# asm.net
KiCad netlist of a schematic drawn in EAGLE
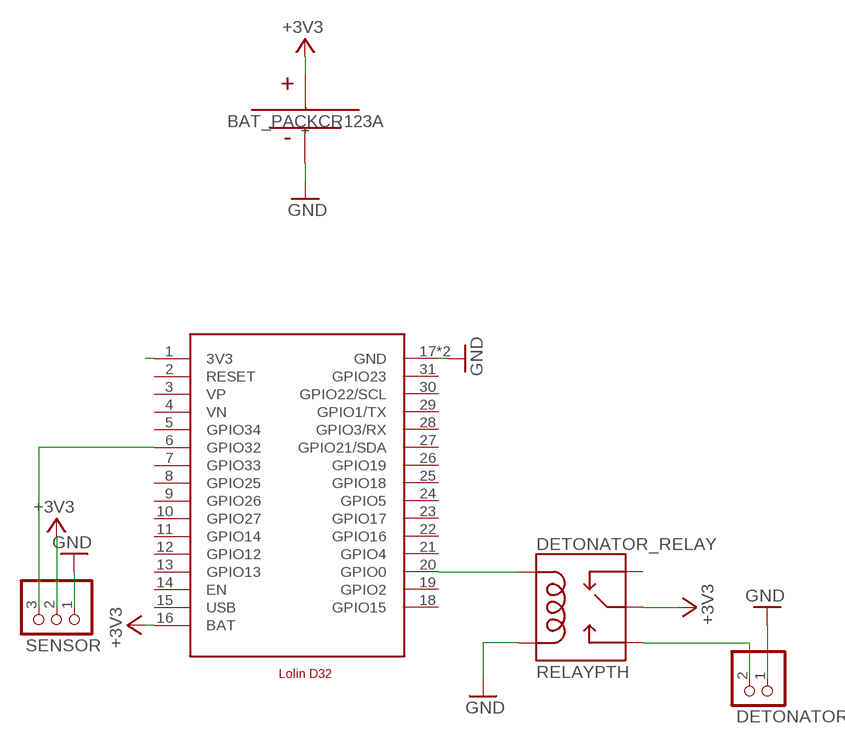
[diagram p0: schematic, sheet 1]

(export (version "E")
  (design (tool "Eeschema 10.0.6"))
  (components
    (comp (ref "CR123A")
      (value "BAT_PACKCR123A")
      (footprint "eagle-import:BH123A")
      (fields (field (name "MANUFACTURER") "MPD") (field (name "MPN") "BH123A"))
      (libsource (lib "eagle-import") (part "BAT_PACKCR123A"))
    )
    (comp (ref "DETONATOR")
      (value "PINHD-1X2")
      (footprint "eagle-import:1X02")
      (libsource (lib "eagle-import") (part "PINHD-1X2"))
    )
    (comp (ref "DETONATOR_RELAY")
      (value "RELAYPTH")
      (footprint "eagle-import:SRD-05VDC-SL-C")
      (libsource (lib "eagle-import") (part "RELAYPTH"))
    )
    (comp (ref "ESP32")
      (value "LOLIND32")
      (footprint "eagle-import:LOLIND32")
      (libsource (lib "eagle-import") (part "LOLIND32"))
    )
    (comp (ref "SENSOR")
      (value "PINHD-1X3")
      (footprint "eagle-import:1X03")
      (libsource (lib "eagle-import") (part "PINHD-1X3"))
    )
  )
  (nets
    (net (code "1") (name "+3V3") (class "Default")
      (node (ref "CR123A") (pin "+") (pinfunction "+_+") (pintype "bidirectional"))
      (node (ref "DETONATOR_RELAY") (pin "SWCOMMON") (pinfunction "SWCOMMON_SWCOMMON") (pintype "bidirectional"))
      (node (ref "ESP32") (pin "16") (pinfunction "BAT_16") (pintype "power_in"))
      (node (ref "SENSOR") (pin "2") (pinfunction "2_2") (pintype "passive"))
    )
    (net (code "2") (name "/USB") (class "Default")
      (node (ref "ESP32") (pin "15") (pinfunction "USB_15") (pintype "power_in"))
    )
    (net (code "3") (name "GND") (class "Default")
      (node (ref "CR123A") (pin "-") (pinfunction "-_-") (pintype "bidirectional"))
      (node (ref "DETONATOR") (pin "1") (pinfunction "1_1") (pintype "passive"))
      (node (ref "DETONATOR_RELAY") (pin "COIL0") (pinfunction "COIL0_COIL0") (pintype "bidirectional"))
      (node (ref "ESP32") (pin "17") (pinfunction "GND_17") (pintype "power_in"))
      (node (ref "ESP32") (pin "32") (pinfunction "GND_32") (pintype "power_in"))
      (node (ref "SENSOR") (pin "1") (pinfunction "1_1") (pintype "passive"))
    )
    (net (code "4") (name "Net-(DETONATOR-Pad2)") (class "Default")
      (node (ref "DETONATOR") (pin "2") (pinfunction "2_2") (pintype "passive"))
      (node (ref "DETONATOR_RELAY") (pin "SWOPEN") (pinfunction "SWOPEN_SWOPEN") (pintype "bidirectional"))
    )
    (net (code "5") (name "Net-(ESP32-GPIO0)") (class "Default")
      (node (ref "DETONATOR_RELAY") (pin "COIL1") (pinfunction "COIL1_COIL1") (pintype "bidirectional"))
      (node (ref "ESP32") (pin "20") (pinfunction "GPIO0_20") (pintype "bidirectional"))
    )
    (net (code "6") (name "Net-(ESP32-GPIO32)") (class "Default")
      (node (ref "ESP32") (pin "6") (pinfunction "GPIO32_6") (pintype "bidirectional"))
      (node (ref "SENSOR") (pin "3") (pinfunction "3_3") (pintype "passive"))
    )
    (net (code "7") (name "unconnected-(DETONATOR_RELAY-SWCLOSE-PadSWCLOSED)") (class "Default")
      (node (ref "DETONATOR_RELAY") (pin "SWCLOSED") (pinfunction "SWCLOSE_SWCLOSED") (pintype "bidirectional"))
    )
    (net (code "8") (name "unconnected-(ESP32-3V3-Pad1)") (class "Default")
      (node (ref "ESP32") (pin "1") (pinfunction "3V3_1") (pintype "power_in"))
    )
    (net (code "9") (name "unconnected-(ESP32-EN-Pad14)") (class "Default")
      (node (ref "ESP32") (pin "14") (pinfunction "EN_14") (pintype "input"))
    )
    (net (code "10") (name "unconnected-(ESP32-GPIO1{slash}TX-Pad29)") (class "Default")
      (node (ref "ESP32") (pin "29") (pinfunction "GPIO1/TX_29") (pintype "bidirectional"))
    )
    (net (code "11") (name "unconnected-(ESP32-GPIO2-Pad19)") (class "Default")
      (node (ref "ESP32") (pin "19") (pinfunction "GPIO2_19") (pintype "bidirectional"))
    )
    (net (code "12") (name "unconnected-(ESP32-GPIO3{slash}RX-Pad28)") (class "Default")
      (node (ref "ESP32") (pin "28") (pinfunction "GPIO3/RX_28") (pintype "bidirectional"))
    )
    (net (code "13") (name "unconnected-(ESP32-GPIO4-Pad21)") (class "Default")
      (node (ref "ESP32") (pin "21") (pinfunction "GPIO4_21") (pintype "bidirectional"))
    )
    (net (code "14") (name "unconnected-(ESP32-GPIO5-Pad24)") (class "Default")
      (node (ref "ESP32") (pin "24") (pinfunction "GPIO5_24") (pintype "bidirectional"))
    )
    (net (code "15") (name "unconnected-(ESP32-GPIO12-Pad12)") (class "Default")
      (node (ref "ESP32") (pin "12") (pinfunction "GPIO12_12") (pintype "bidirectional"))
    )
    (net (code "16") (name "unconnected-(ESP32-GPIO13-Pad13)") (class "Default")
      (node (ref "ESP32") (pin "13") (pinfunction "GPIO13_13") (pintype "bidirectional"))
    )
    (net (code "17") (name "unconnected-(ESP32-GPIO14-Pad11)") (class "Default")
      (node (ref "ESP32") (pin "11") (pinfunction "GPIO14_11") (pintype "bidirectional"))
    )
    (net (code "18") (name "unconnected-(ESP32-GPIO15-Pad18)") (class "Default")
      (node (ref "ESP32") (pin "18") (pinfunction "GPIO15_18") (pintype "bidirectional"))
    )
    (net (code "19") (name "unconnected-(ESP32-GPIO16-Pad22)") (class "Default")
      (node (ref "ESP32") (pin "22") (pinfunction "GPIO16_22") (pintype "bidirectional"))
    )
    (net (code "20") (name "unconnected-(ESP32-GPIO17-Pad23)") (class "Default")
      (node (ref "ESP32") (pin "23") (pinfunction "GPIO17_23") (pintype "bidirectional"))
    )
    (net (code "21") (name "unconnected-(ESP32-GPIO18-Pad25)") (class "Default")
      (node (ref "ESP32") (pin "25") (pinfunction "GPIO18_25") (pintype "bidirectional"))
    )
    (net (code "22") (name "unconnected-(ESP32-GPIO19-Pad26)") (class "Default")
      (node (ref "ESP32") (pin "26") (pinfunction "GPIO19_26") (pintype "bidirectional"))
    )
    (net (code "23") (name "unconnected-(ESP32-GPIO21{slash}SDA-Pad27)") (class "Default")
      (node (ref "ESP32") (pin "27") (pinfunction "GPIO21/SDA_27") (pintype "bidirectional"))
    )
    (net (code "24") (name "unconnected-(ESP32-GPIO22{slash}SCL-Pad30)") (class "Default")
      (node (ref "ESP32") (pin "30") (pinfunction "GPIO22/SCL_30") (pintype "bidirectional"))
    )
    (net (code "25") (name "unconnected-(ESP32-GPIO23-Pad31)") (class "Default")
      (node (ref "ESP32") (pin "31") (pinfunction "GPIO23_31") (pintype "bidirectional"))
    )
    (net (code "26") (name "unconnected-(ESP32-GPIO25-Pad8)") (class "Default")
      (node (ref "ESP32") (pin "8") (pinfunction "GPIO25_8") (pintype "bidirectional"))
    )
    (net (code "27") (name "unconnected-(ESP32-GPIO26-Pad9)") (class "Default")
      (node (ref "ESP32") (pin "9") (pinfunction "GPIO26_9") (pintype "bidirectional"))
    )
    (net (code "28") (name "unconnected-(ESP32-GPIO27-Pad10)") (class "Default")
      (node (ref "ESP32") (pin "10") (pinfunction "GPIO27_10") (pintype "bidirectional"))
    )
    (net (code "29") (name "unconnected-(ESP32-GPIO33-Pad7)") (class "Default")
      (node (ref "ESP32") (pin "7") (pinfunction "GPIO33_7") (pintype "bidirectional"))
    )
    (net (code "30") (name "unconnected-(ESP32-GPIO34-Pad5)") (class "Default")
      (node (ref "ESP32") (pin "5") (pinfunction "GPIO34_5") (pintype "input"))
    )
    (net (code "31") (name "unconnected-(ESP32-RESET-Pad2)") (class "Default")
      (node (ref "ESP32") (pin "2") (pinfunction "RESET_2") (pintype "input"))
    )
    (net (code "32") (name "unconnected-(ESP32-VN-Pad4)") (class "Default")
      (node (ref "ESP32") (pin "4") (pinfunction "VN_4") (pintype "no_connect"))
    )
    (net (code "33") (name "unconnected-(ESP32-VP-Pad3)") (class "Default")
      (node (ref "ESP32") (pin "3") (pinfunction "VP_3") (pintype "no_connect"))
    )
  )
)
